# pierce-test-board4.net
KiCad netlist of a schematic drawn in EAGLE
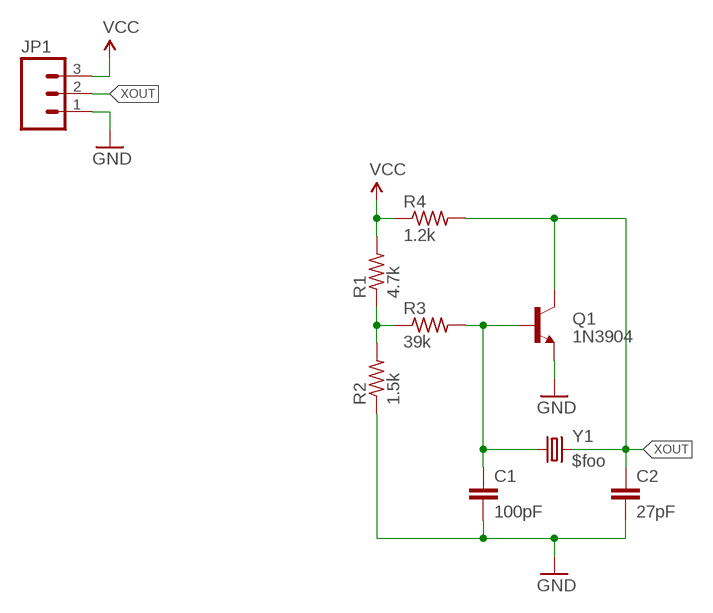
[diagram p0: schematic, sheet 1]

(export (version "E")
  (design (tool "Eeschema 10.0.6"))
  (components
    (comp (ref "C1")
      (value "100pF")
      (footprint "eagle-import:C025-024X044")
      (libsource (lib "eagle-import") (part "CAPACITOR-CERAMIC025-024X044"))
    )
    (comp (ref "C2")
      (value "27pF")
      (footprint "eagle-import:C025-024X044")
      (libsource (lib "eagle-import") (part "CAPACITOR-CERAMIC025-024X044"))
    )
    (comp (ref "JP1")
      (value "M03PTH")
      (footprint "eagle-import:1X03")
      (libsource (lib "eagle-import") (part "M03PTH"))
    )
    (comp (ref "Q1")
      (value "1N3904")
      (footprint "eagle-import:TO-92-AMMO")
      (libsource (lib "eagle-import") (part "TRANSISTOR_NPNTO-92-AMMO-EBC"))
    )
    (comp (ref "R1")
      (value "4.7k")
      (footprint "eagle-import:RESISTOR-AXIAL-PTH-5.08MM")
      (libsource (lib "eagle-import") (part "RESISTORPTH-AXIAL-5.08MM"))
    )
    (comp (ref "R2")
      (value "1.5k")
      (footprint "eagle-import:RESISTOR-AXIAL-PTH-5.08MM")
      (libsource (lib "eagle-import") (part "RESISTORPTH-AXIAL-5.08MM"))
    )
    (comp (ref "R3")
      (value "39k")
      (footprint "eagle-import:RESISTOR-AXIAL-PTH-5.08MM")
      (libsource (lib "eagle-import") (part "RESISTORPTH-AXIAL-5.08MM"))
    )
    (comp (ref "R4")
      (value "1.2k")
      (footprint "eagle-import:RESISTOR-AXIAL-PTH-5.08MM")
      (libsource (lib "eagle-import") (part "RESISTORPTH-AXIAL-5.08MM"))
    )
    (comp (ref "Y1")
      (value "$foo")
      (footprint "eagle-import:HC49U-V")
      (libsource (lib "eagle-import") (part "CRYSTALHC49UV"))
    )
  )
  (nets
    (net (code "1") (name "GND") (class "Default")
      (node (ref "C1") (pin "2") (pinfunction "2_2") (pintype "passive"))
      (node (ref "C2") (pin "2") (pinfunction "2_2") (pintype "passive"))
      (node (ref "JP1") (pin "1") (pinfunction "1_1") (pintype "passive"))
      (node (ref "Q1") (pin "1") (pinfunction "E_1") (pintype "passive"))
      (node (ref "R2") (pin "P$1") (pinfunction "1_P$1") (pintype "passive"))
    )
    (net (code "2") (name "Net-(Q1-B)") (class "Default")
      (node (ref "C1") (pin "1") (pinfunction "1_1") (pintype "passive"))
      (node (ref "Q1") (pin "2") (pinfunction "B_2") (pintype "passive"))
      (node (ref "R3") (pin "P$2") (pinfunction "2_P$2") (pintype "passive"))
      (node (ref "Y1") (pin "1") (pinfunction "1_1") (pintype "passive"))
    )
    (net (code "3") (name "Net-(R1-1)") (class "Default")
      (node (ref "R1") (pin "P$1") (pinfunction "1_P$1") (pintype "passive"))
      (node (ref "R2") (pin "P$2") (pinfunction "2_P$2") (pintype "passive"))
      (node (ref "R3") (pin "P$1") (pinfunction "1_P$1") (pintype "passive"))
    )
    (net (code "4") (name "VCC") (class "Default")
      (node (ref "JP1") (pin "3") (pinfunction "3_3") (pintype "passive"))
      (node (ref "R1") (pin "P$2") (pinfunction "2_P$2") (pintype "passive"))
      (node (ref "R4") (pin "P$1") (pinfunction "1_P$1") (pintype "passive"))
    )
    (net (code "5") (name "XOUT") (class "Default")
      (node (ref "C2") (pin "1") (pinfunction "1_1") (pintype "passive"))
      (node (ref "JP1") (pin "2") (pinfunction "2_2") (pintype "passive"))
      (node (ref "Q1") (pin "3") (pinfunction "C_3") (pintype "passive"))
      (node (ref "R4") (pin "P$2") (pinfunction "2_P$2") (pintype "passive"))
      (node (ref "Y1") (pin "2") (pinfunction "2_2") (pintype "passive"))
    )
  )
)
